# WalkerStalkerv21.net
KiCad netlist of a schematic drawn in EAGLE
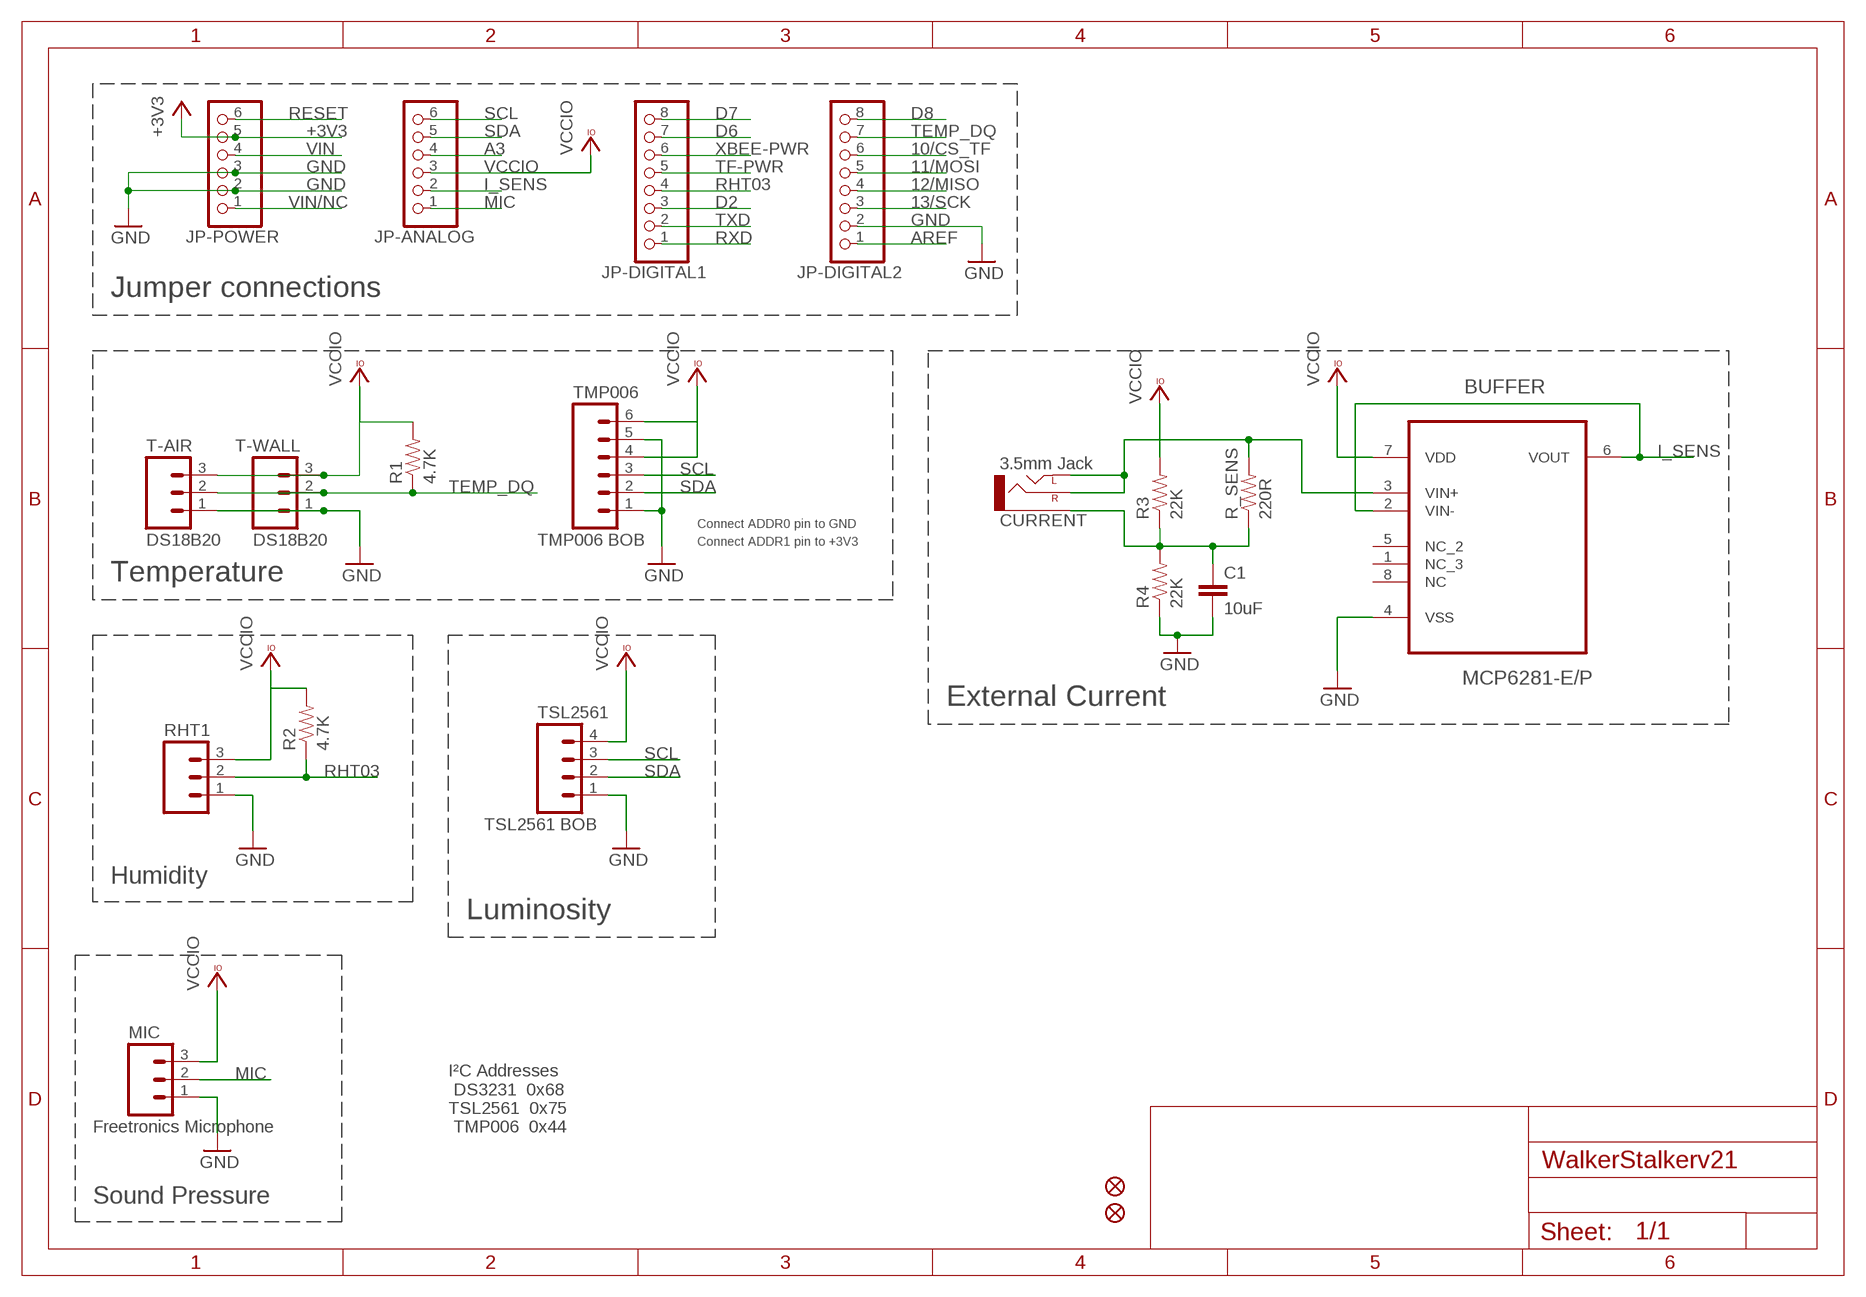
[diagram p0: schematic, sheet 1, part 1 of 2]
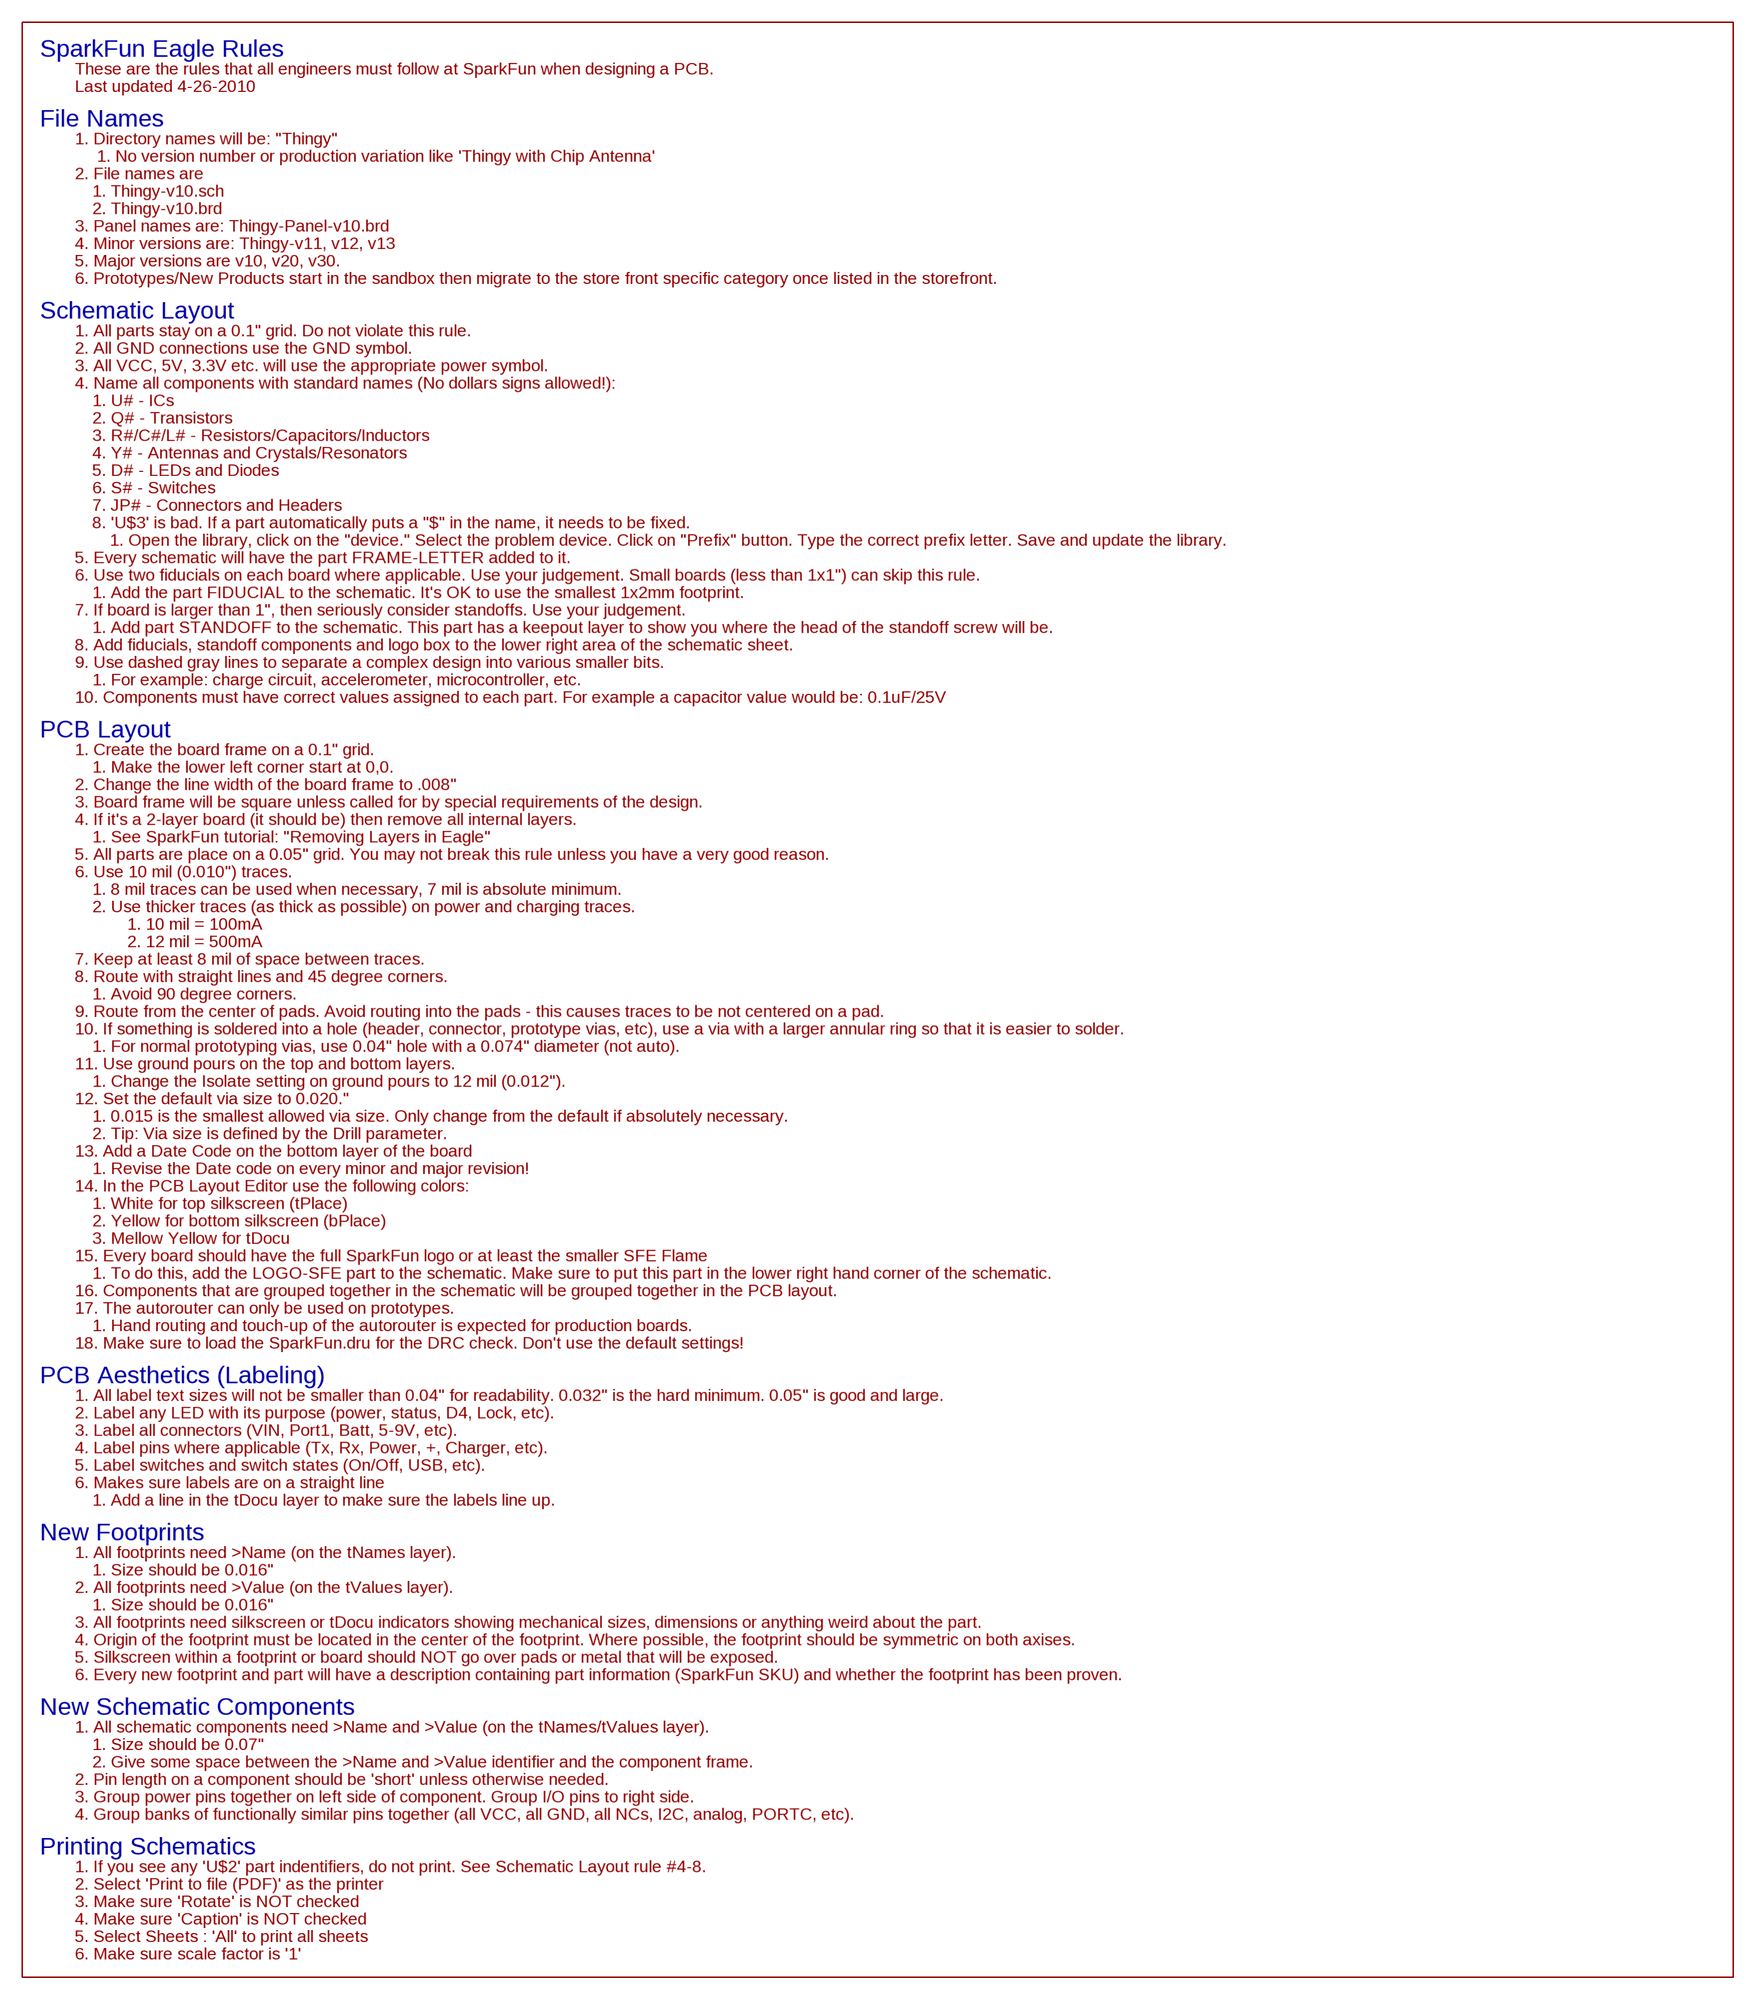
[diagram p1: schematic, sheet 1, part 2 of 2]

(export (version "E")
  (design (tool "Eeschema 10.0.6"))
  (components
    (comp (ref "BUFFER")
      (value "MCP6281-E/P")
      (footprint "eagle-import:DIP254P762X432-8")
      (libsource (lib "eagle-import") (part "MCP6281-E/P"))
    )
    (comp (ref "C1")
      (value "10uF")
      (footprint "eagle-import:1206")
      (libsource (lib "eagle-import") (part "CAP1206"))
    )
    (comp (ref "CURRENT")
      (value "3.5mm Jack")
      (footprint "eagle-import:AUDIO-JACK")
      (libsource (lib "eagle-import") (part "AUDIO-JACKPTH"))
    )
    (comp (ref "FID1")
      (value "FIDUCIAL1.5X3")
      (footprint "eagle-import:FIDUCIAL-1.5X3")
      (libsource (lib "eagle-import") (part "FIDUCIAL1.5X3"))
    )
    (comp (ref "FID2")
      (value "FIDUCIAL1.5X3")
      (footprint "eagle-import:FIDUCIAL-1.5X3")
      (libsource (lib "eagle-import") (part "FIDUCIAL1.5X3"))
    )
    (comp (ref "JP-ANALOG")
      (value "PINHD-1X6CB")
      (footprint "eagle-import:1X06-CLEANBIG")
      (libsource (lib "eagle-import") (part "PINHD-1X6CB"))
    )
    (comp (ref "JP-DIGITAL1")
      (value "PINHD-1X8CLEANBIG")
      (footprint "eagle-import:1X08-CLEANBIG")
      (libsource (lib "eagle-import") (part "PINHD-1X8CLEANBIG"))
    )
    (comp (ref "JP-DIGITAL2")
      (value "PINHD-1X8CLEANBIG")
      (footprint "eagle-import:1X08-CLEANBIG")
      (libsource (lib "eagle-import") (part "PINHD-1X8CLEANBIG"))
    )
    (comp (ref "JP-POWER")
      (value "PINHD-1X6CB")
      (footprint "eagle-import:1X06-CLEANBIG")
      (libsource (lib "eagle-import") (part "PINHD-1X6CB"))
    )
    (comp (ref "MIC")
      (value "Freetronics Microphone")
      (footprint "eagle-import:1X03")
      (libsource (lib "eagle-import") (part "M03PTH"))
    )
    (comp (ref "R1")
      (value "4.7K")
      (footprint "eagle-import:1206")
      (libsource (lib "eagle-import") (part "RESISTOR1206"))
    )
    (comp (ref "R2")
      (value "4.7K")
      (footprint "eagle-import:1206")
      (libsource (lib "eagle-import") (part "RESISTOR1206"))
    )
    (comp (ref "R3")
      (value "22K")
      (footprint "eagle-import:1206")
      (libsource (lib "eagle-import") (part "RESISTOR1206"))
    )
    (comp (ref "R4")
      (value "22K")
      (footprint "eagle-import:1206")
      (libsource (lib "eagle-import") (part "RESISTOR1206"))
    )
    (comp (ref "RHT1")
      (value "RHT03")
      (footprint "eagle-import:1X03")
      (libsource (lib "eagle-import") (part "M03PTH"))
    )
    (comp (ref "R_SENS")
      (value "220R")
      (footprint "eagle-import:1206")
      (libsource (lib "eagle-import") (part "RESISTOR1206"))
    )
    (comp (ref "T-AIR")
      (value "DS18B20")
      (footprint "eagle-import:1X03")
      (libsource (lib "eagle-import") (part "M03PTH"))
    )
    (comp (ref "T-WALL")
      (value "DS18B20")
      (footprint "eagle-import:1X03")
      (libsource (lib "eagle-import") (part "M03PTH"))
    )
    (comp (ref "TMP006")
      (value "TMP006 BOB")
      (footprint "eagle-import:1X06")
      (libsource (lib "eagle-import") (part "M06SIP"))
    )
    (comp (ref "TSL2561")
      (value "TSL2561 BOB")
      (footprint "eagle-import:1X04")
      (libsource (lib "eagle-import") (part "M04PTH"))
    )
  )
  (nets
    (net (code "1") (name "+3V3") (class "Default")
      (node (ref "JP-POWER") (pin "5") (pinfunction "5_5") (pintype "passive"))
    )
    (net (code "2") (name "/10{slash}CS_TF") (class "Default")
      (node (ref "JP-DIGITAL2") (pin "6") (pinfunction "6_6") (pintype "passive"))
    )
    (net (code "3") (name "/11{slash}MOSI") (class "Default")
      (node (ref "JP-DIGITAL2") (pin "5") (pinfunction "5_5") (pintype "passive"))
    )
    (net (code "4") (name "/12{slash}MISO") (class "Default")
      (node (ref "JP-DIGITAL2") (pin "4") (pinfunction "4_4") (pintype "passive"))
    )
    (net (code "5") (name "/13{slash}SCK") (class "Default")
      (node (ref "JP-DIGITAL2") (pin "3") (pinfunction "3_3") (pintype "passive"))
    )
    (net (code "6") (name "/A3") (class "Default")
      (node (ref "JP-ANALOG") (pin "4") (pinfunction "4_4") (pintype "passive"))
    )
    (net (code "7") (name "/AREF") (class "Default")
      (node (ref "JP-DIGITAL2") (pin "1") (pinfunction "1_1") (pintype "passive"))
    )
    (net (code "8") (name "/D2") (class "Default")
      (node (ref "JP-DIGITAL1") (pin "3") (pinfunction "3_3") (pintype "passive"))
    )
    (net (code "9") (name "/D6") (class "Default")
      (node (ref "JP-DIGITAL1") (pin "7") (pinfunction "7_7") (pintype "passive"))
    )
    (net (code "10") (name "/D7") (class "Default")
      (node (ref "JP-DIGITAL1") (pin "8") (pinfunction "8_8") (pintype "passive"))
    )
    (net (code "11") (name "/D8") (class "Default")
      (node (ref "JP-DIGITAL2") (pin "8") (pinfunction "8_8") (pintype "passive"))
    )
    (net (code "12") (name "/I_SENS") (class "Default")
      (node (ref "BUFFER") (pin "2") (pinfunction "VIN-_2") (pintype "input"))
      (node (ref "BUFFER") (pin "6") (pinfunction "VOUT_6") (pintype "output"))
      (node (ref "JP-ANALOG") (pin "2") (pinfunction "2_2") (pintype "passive"))
    )
    (net (code "13") (name "/MIC") (class "Default")
      (node (ref "JP-ANALOG") (pin "1") (pinfunction "1_1") (pintype "passive"))
      (node (ref "MIC") (pin "2") (pinfunction "2_2") (pintype "passive"))
    )
    (net (code "14") (name "/RESET") (class "Default")
      (node (ref "JP-POWER") (pin "6") (pinfunction "6_6") (pintype "passive"))
    )
    (net (code "15") (name "/RHT03") (class "Default")
      (node (ref "JP-DIGITAL1") (pin "4") (pinfunction "4_4") (pintype "passive"))
      (node (ref "R2") (pin "1") (pinfunction "1_1") (pintype "passive"))
      (node (ref "RHT1") (pin "2") (pinfunction "2_2") (pintype "passive"))
    )
    (net (code "16") (name "/RXD") (class "Default")
      (node (ref "JP-DIGITAL1") (pin "1") (pinfunction "1_1") (pintype "passive"))
    )
    (net (code "17") (name "/SCL") (class "Default")
      (node (ref "JP-ANALOG") (pin "6") (pinfunction "6_6") (pintype "passive"))
      (node (ref "TMP006") (pin "3") (pinfunction "3_3") (pintype "passive"))
      (node (ref "TSL2561") (pin "3") (pinfunction "3_3") (pintype "passive"))
    )
    (net (code "18") (name "/SDA") (class "Default")
      (node (ref "JP-ANALOG") (pin "5") (pinfunction "5_5") (pintype "passive"))
      (node (ref "TMP006") (pin "2") (pinfunction "2_2") (pintype "passive"))
      (node (ref "TSL2561") (pin "2") (pinfunction "2_2") (pintype "passive"))
    )
    (net (code "19") (name "/TEMP_DQ") (class "Default")
      (node (ref "JP-DIGITAL2") (pin "7") (pinfunction "7_7") (pintype "passive"))
      (node (ref "R1") (pin "1") (pinfunction "1_1") (pintype "passive"))
      (node (ref "T-AIR") (pin "2") (pinfunction "2_2") (pintype "passive"))
      (node (ref "T-WALL") (pin "2") (pinfunction "2_2") (pintype "passive"))
    )
    (net (code "20") (name "/TF-PWR") (class "Default")
      (node (ref "JP-DIGITAL1") (pin "5") (pinfunction "5_5") (pintype "passive"))
    )
    (net (code "21") (name "/TXD") (class "Default")
      (node (ref "JP-DIGITAL1") (pin "2") (pinfunction "2_2") (pintype "passive"))
    )
    (net (code "22") (name "/VIN") (class "Default")
      (node (ref "JP-POWER") (pin "4") (pinfunction "4_4") (pintype "passive"))
    )
    (net (code "23") (name "/VIN{slash}NC") (class "Default")
      (node (ref "JP-POWER") (pin "1") (pinfunction "1_1") (pintype "passive"))
    )
    (net (code "24") (name "/XBEE-PWR") (class "Default")
      (node (ref "JP-DIGITAL1") (pin "6") (pinfunction "6_6") (pintype "passive"))
    )
    (net (code "25") (name "GND") (class "Default")
      (node (ref "BUFFER") (pin "4") (pinfunction "VSS_4") (pintype "power_in"))
      (node (ref "C1") (pin "2") (pinfunction "2_2") (pintype "passive"))
      (node (ref "JP-DIGITAL2") (pin "2") (pinfunction "2_2") (pintype "passive"))
      (node (ref "JP-POWER") (pin "2") (pinfunction "2_2") (pintype "passive"))
      (node (ref "JP-POWER") (pin "3") (pinfunction "3_3") (pintype "passive"))
      (node (ref "MIC") (pin "1") (pinfunction "1_1") (pintype "passive"))
      (node (ref "R4") (pin "1") (pinfunction "1_1") (pintype "passive"))
      (node (ref "RHT1") (pin "1") (pinfunction "1_1") (pintype "passive"))
      (node (ref "T-AIR") (pin "1") (pinfunction "1_1") (pintype "passive"))
      (node (ref "T-WALL") (pin "1") (pinfunction "1_1") (pintype "passive"))
      (node (ref "TMP006") (pin "1") (pinfunction "1_1") (pintype "passive"))
      (node (ref "TMP006") (pin "5") (pinfunction "5_5") (pintype "passive"))
      (node (ref "TSL2561") (pin "1") (pinfunction "1_1") (pintype "passive"))
    )
    (net (code "26") (name "Net-(BUFFER-VIN+)") (class "Default")
      (node (ref "BUFFER") (pin "3") (pinfunction "VIN+_3") (pintype "input"))
      (node (ref "CURRENT") (pin "RING") (pinfunction "RIGHT_RING") (pintype "bidirectional"))
      (node (ref "CURRENT") (pin "TIP") (pinfunction "LEFT_TIP") (pintype "bidirectional"))
      (node (ref "R_SENS") (pin "2") (pinfunction "2_2") (pintype "passive"))
    )
    (net (code "27") (name "Net-(C1-Pad1)") (class "Default")
      (node (ref "C1") (pin "1") (pinfunction "1_1") (pintype "passive"))
      (node (ref "CURRENT") (pin "SLEEVE") (pinfunction "SLEEVE_SLEEVE") (pintype "bidirectional"))
      (node (ref "R3") (pin "1") (pinfunction "1_1") (pintype "passive"))
      (node (ref "R4") (pin "2") (pinfunction "2_2") (pintype "passive"))
      (node (ref "R_SENS") (pin "1") (pinfunction "1_1") (pintype "passive"))
    )
    (net (code "28") (name "VCCIO") (class "Default")
      (node (ref "BUFFER") (pin "7") (pinfunction "VDD_7") (pintype "power_in"))
      (node (ref "JP-ANALOG") (pin "3") (pinfunction "3_3") (pintype "passive"))
      (node (ref "MIC") (pin "3") (pinfunction "3_3") (pintype "passive"))
      (node (ref "R1") (pin "2") (pinfunction "2_2") (pintype "passive"))
      (node (ref "R2") (pin "2") (pinfunction "2_2") (pintype "passive"))
      (node (ref "R3") (pin "2") (pinfunction "2_2") (pintype "passive"))
      (node (ref "RHT1") (pin "3") (pinfunction "3_3") (pintype "passive"))
      (node (ref "T-AIR") (pin "3") (pinfunction "3_3") (pintype "passive"))
      (node (ref "T-WALL") (pin "3") (pinfunction "3_3") (pintype "passive"))
      (node (ref "TMP006") (pin "4") (pinfunction "4_4") (pintype "passive"))
      (node (ref "TMP006") (pin "6") (pinfunction "6_6") (pintype "passive"))
      (node (ref "TSL2561") (pin "4") (pinfunction "4_4") (pintype "passive"))
    )
    (net (code "29") (name "unconnected-(BUFFER-NC-Pad8)") (class "Default")
      (node (ref "BUFFER") (pin "8") (pinfunction "NC_8") (pintype "no_connect"))
    )
    (net (code "30") (name "unconnected-(BUFFER-NC_2-Pad5)") (class "Default")
      (node (ref "BUFFER") (pin "5") (pinfunction "NC_2_5") (pintype "no_connect"))
    )
    (net (code "31") (name "unconnected-(BUFFER-NC_3-Pad1)") (class "Default")
      (node (ref "BUFFER") (pin "1") (pinfunction "NC_3_1") (pintype "no_connect"))
    )
  )
)
